# Power_Schematic.net
KiCad netlist of a schematic drawn in Altium Designer
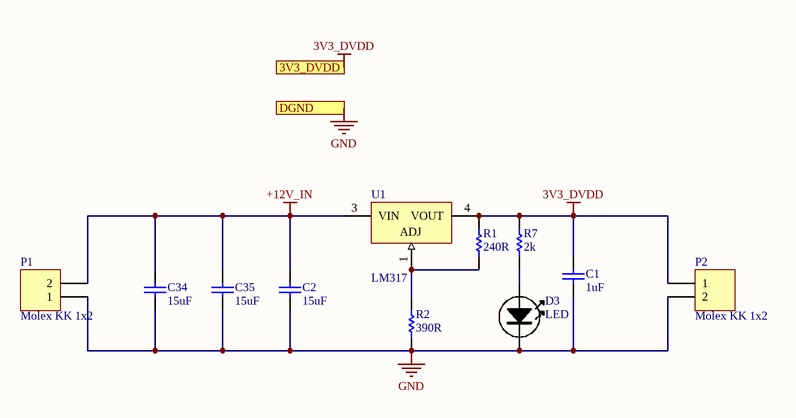
[diagram p0: Power_Schematic.SchDoc]

(export (version "E")
  (design (tool "Eeschema 10.0.6"))
  (components
    (comp (ref "C1")
      (value "1uF")
      (footprint "C0805")
      (description "0805 Capacitor")
      (libsource (lib "PARSEC") (part "C0805"))
    )
    (comp (ref "C2")
      (value "15uF")
      (footprint "C0805")
      (description "0805 Capacitor")
      (libsource (lib "PARSEC") (part "C0805"))
    )
    (comp (ref "C34")
      (value "15uF")
      (footprint "C0805")
      (description "0805 Capacitor")
      (libsource (lib "PARSEC") (part "C0805"))
    )
    (comp (ref "C35")
      (value "15uF")
      (footprint "C0805")
      (description "0805 Capacitor")
      (libsource (lib "PARSEC") (part "C0805"))
    )
    (comp (ref "D3")
      (value "LED")
      (footprint "0805LED")
      (fields
        (field (name "MANUFACTURER") "OSRAM Opto Semiconductors Inc")
        (field (name "MANUFACTURER PART NUMBER") "LS T676-Q1R2-1-Z")
      )
      (libsource (lib "PARSEC") (part "LED"))
    )
    (comp (ref "P1")
      (value "Molex KK 1x2")
      (footprint "Molex KK 2x1")
      (description "1x2 Molex KK Connector")
      (libsource (lib "") (part "Molex KK 1x2_1"))
    )
    (comp (ref "P2")
      (value "Molex KK 1x2")
      (footprint "Molex KK 2x1")
      (description "1x2 Molex KK Connector")
      (libsource (lib "PARSEC") (part "Molex KK 1x2"))
    )
    (comp (ref "R1")
      (value "240R")
      (footprint "R0805")
      (description "RESISTOR 0805")
      (libsource (lib "PARSEC") (part "R0805"))
    )
    (comp (ref "R2")
      (value "390R")
      (footprint "R0805")
      (description "RESISTOR 0805")
      (libsource (lib "PARSEC") (part "R0805"))
    )
    (comp (ref "R7")
      (value "2k")
      (footprint "R0805")
      (description "RESISTOR 0805")
      (libsource (lib "PARSEC") (part "R0805"))
    )
    (comp (ref "U1")
      (value "LM317")
      (footprint "D-PAK")
      (description "Linear Voltage Regulator")
      (libsource (lib "PARSEC") (part "LM317"))
    )
  )
  (nets
    (net (code "1") (name "+12V_IN") (class "Default")
      (node (ref "C2") (pin "1") (pinfunction "1_1") (pintype "passive"))
      (node (ref "C34") (pin "1") (pinfunction "1_1") (pintype "passive"))
      (node (ref "C35") (pin "1") (pinfunction "1_1") (pintype "passive"))
      (node (ref "P1") (pin "2") (pinfunction "2_2") (pintype "passive"))
      (node (ref "U1") (pin "3") (pinfunction "VIN_3") (pintype "power_in"))
    )
    (net (code "2") (name "3V3_DVDD") (class "Default")
      (node (ref "C1") (pin "1") (pinfunction "1_1") (pintype "passive"))
      (node (ref "P2") (pin "1") (pinfunction "1_1") (pintype "passive"))
      (node (ref "R1") (pin "2") (pinfunction "2_2") (pintype "passive"))
      (node (ref "R7") (pin "2") (pinfunction "2_2") (pintype "passive"))
      (node (ref "U1") (pin "4") (pinfunction "VOUT_4") (pintype "power_in"))
    )
    (net (code "3") (name "GND") (class "Default")
      (node (ref "C1") (pin "2") (pinfunction "2_2") (pintype "passive"))
      (node (ref "C2") (pin "2") (pinfunction "2_2") (pintype "passive"))
      (node (ref "C34") (pin "2") (pinfunction "2_2") (pintype "passive"))
      (node (ref "C35") (pin "2") (pinfunction "2_2") (pintype "passive"))
      (node (ref "D3") (pin "K") (pintype "passive"))
      (node (ref "P1") (pin "1") (pinfunction "1_1") (pintype "passive"))
      (node (ref "P2") (pin "2") (pinfunction "2_2") (pintype "passive"))
      (node (ref "R2") (pin "1") (pinfunction "1_1") (pintype "passive"))
    )
    (net (code "4") (name "Net-(D3-PadA)") (class "Default")
      (node (ref "D3") (pin "A") (pintype "passive"))
      (node (ref "R7") (pin "1") (pinfunction "1_1") (pintype "passive"))
    )
    (net (code "5") (name "Net-(U1-ADJ)") (class "Default")
      (node (ref "R1") (pin "1") (pinfunction "1_1") (pintype "passive"))
      (node (ref "R2") (pin "2") (pinfunction "2_2") (pintype "passive"))
      (node (ref "U1") (pin "1") (pinfunction "ADJ_1") (pintype "input"))
    )
  )
)
